# minigame.net
KiCad netlist of a schematic drawn in EAGLE
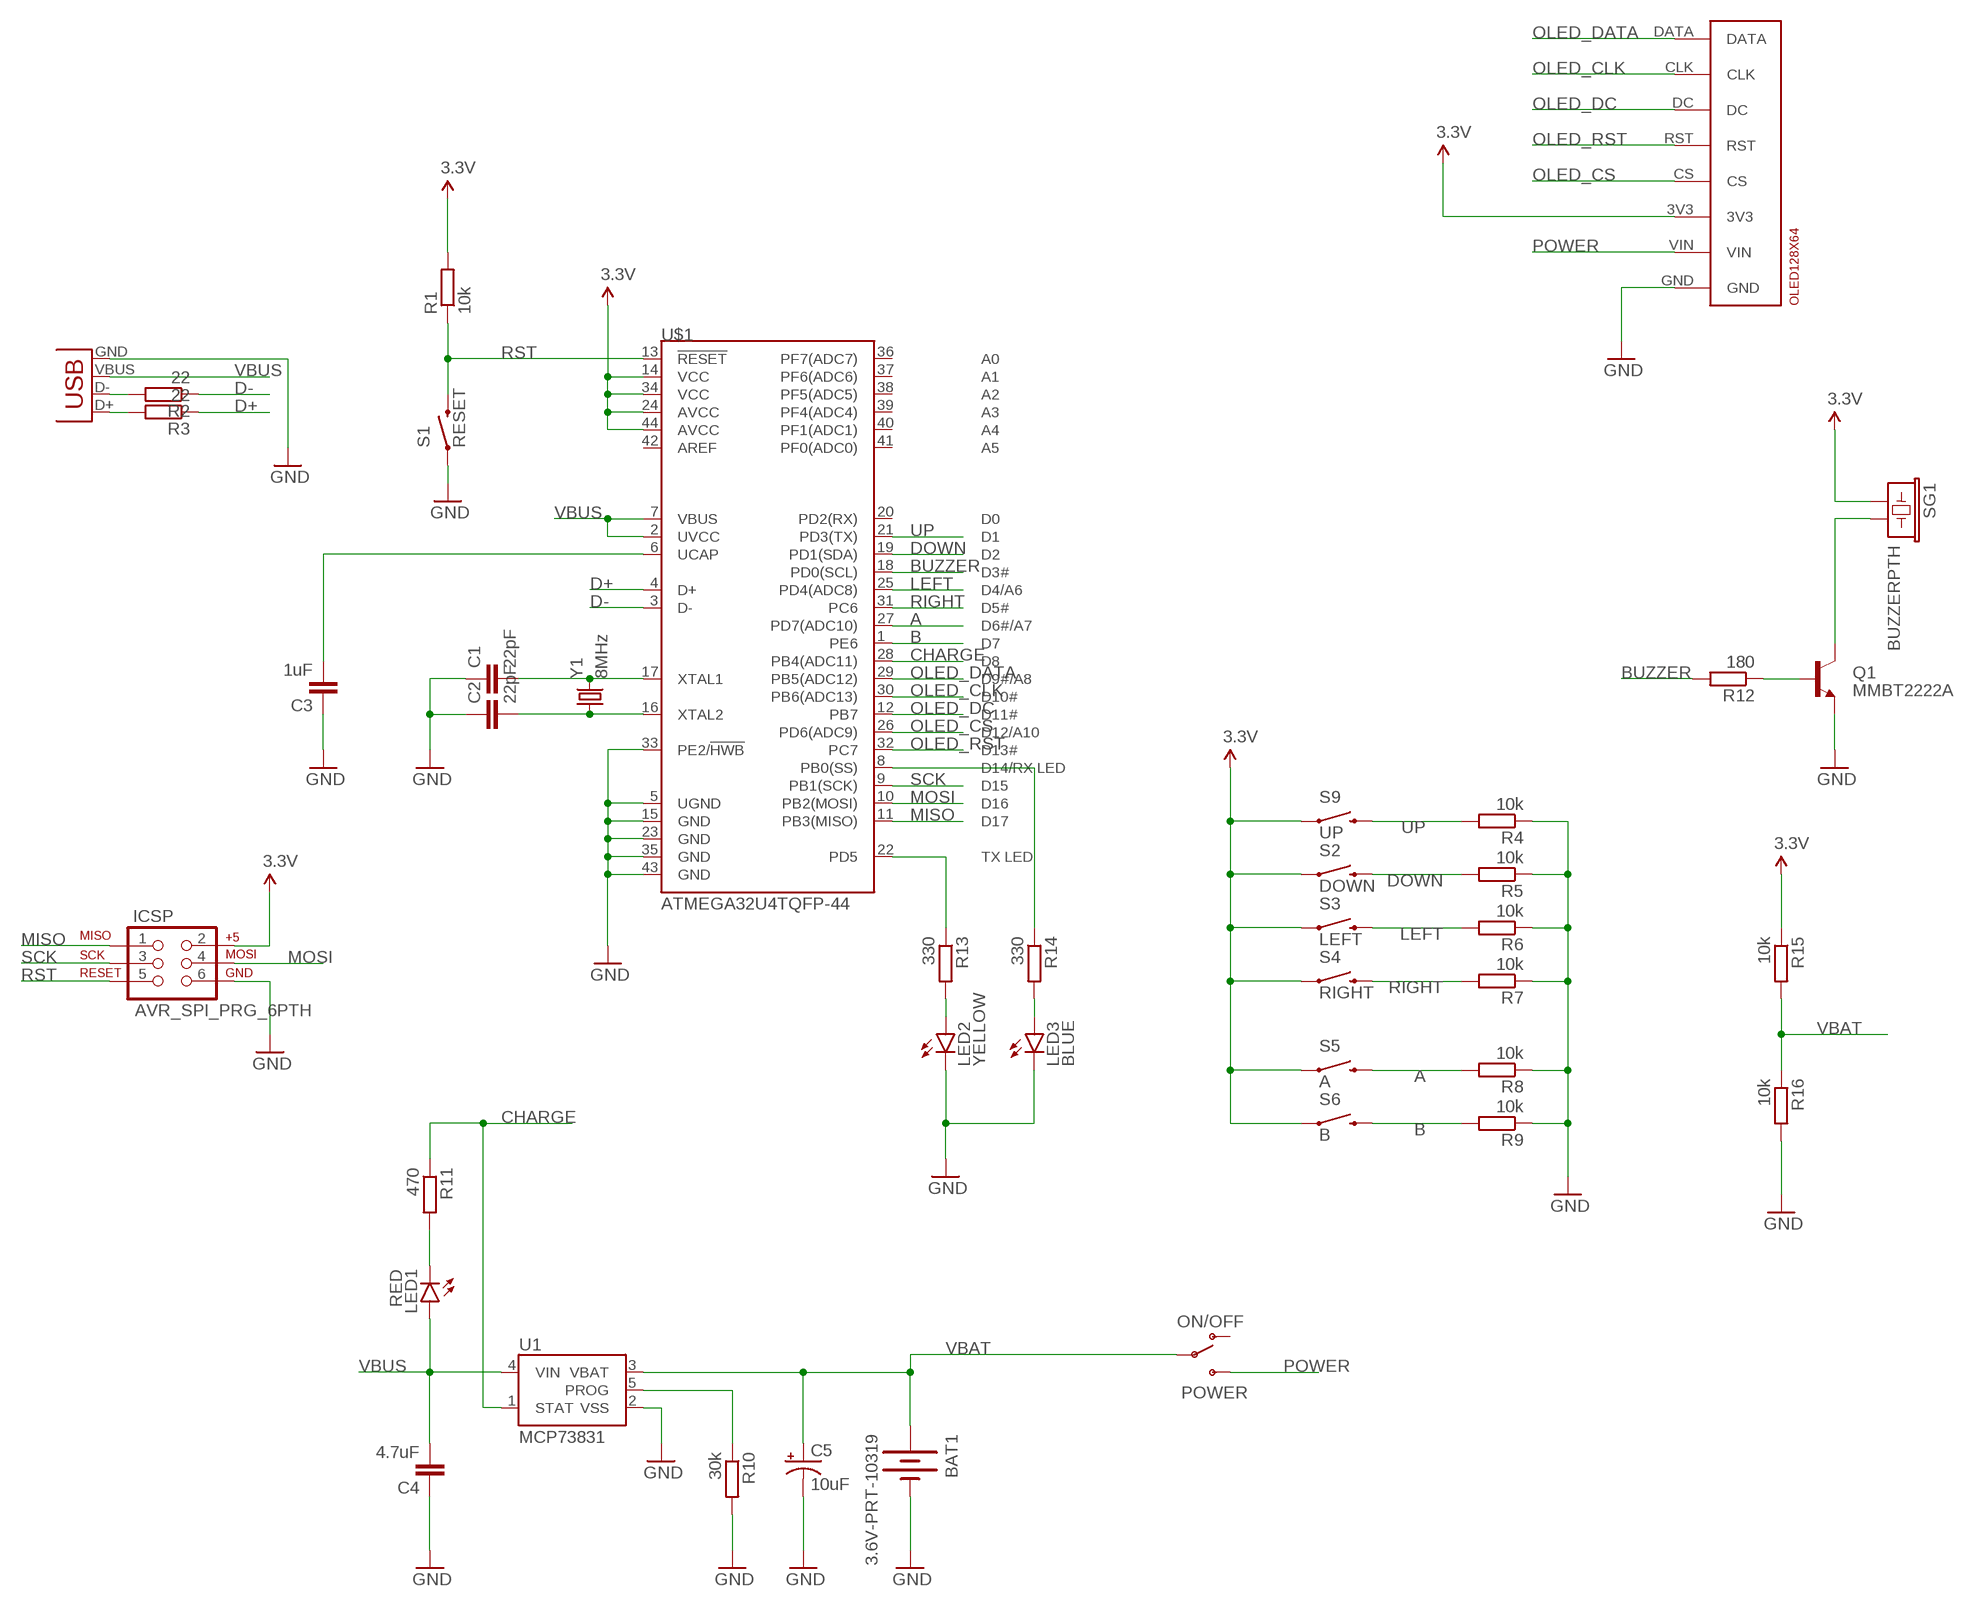
[diagram p0: schematic, sheet 1]

(export (version "E")
  (design (tool "Eeschema 10.0.6"))
  (components
    (comp (ref "BAT1")
      (value "3.6V-PRT-10319")
      (footprint "eagle-import:BATTCON_245MM_PTH")
      (libsource (lib "eagle-import") (part "BATTERY245PTH"))
    )
    (comp (ref "C1")
      (value "22pF")
      (footprint "eagle-import:1206")
      (libsource (lib "eagle-import") (part "CAP1206"))
    )
    (comp (ref "C2")
      (value "22pF")
      (footprint "eagle-import:1206")
      (libsource (lib "eagle-import") (part "CAP1206"))
    )
    (comp (ref "C3")
      (value "1uF")
      (footprint "eagle-import:1206")
      (libsource (lib "eagle-import") (part "CAP1206"))
    )
    (comp (ref "C4")
      (value "4.7uF")
      (footprint "eagle-import:1206")
      (libsource (lib "eagle-import") (part "CAP1206"))
    )
    (comp (ref "C5")
      (value "10uF")
      (footprint "eagle-import:PANASONIC_D")
      (libsource (lib "eagle-import") (part "CAP_POLD"))
    )
    (comp (ref "ICSP")
      (value "AVR_SPI_PRG_6PTH")
      (footprint "eagle-import:2X3")
      (libsource (lib "eagle-import") (part "AVR_SPI_PRG_6PTH"))
    )
    (comp (ref "JP1")
      (value "USB-SMD-NS")
      (footprint "eagle-import:USB-MINIB-NOSTOP")
      (libsource (lib "eagle-import") (part "USB-SMD-NS"))
    )
    (comp (ref "LED1")
      (value "RED")
      (footprint "eagle-import:LED-0603")
      (libsource (lib "eagle-import") (part "LED0603"))
    )
    (comp (ref "LED2")
      (value "YELLOW")
      (footprint "eagle-import:LED-0603")
      (libsource (lib "eagle-import") (part "LED0603"))
    )
    (comp (ref "LED3")
      (value "BLUE")
      (footprint "eagle-import:LED-0603")
      (libsource (lib "eagle-import") (part "LED0603"))
    )
    (comp (ref "OLED128X64")
      (value "OLED128X64-ADAFRUIT938")
      (footprint "eagle-import:938")
      (libsource (lib "eagle-import") (part "OLED128X64-ADAFRUIT938"))
    )
    (comp (ref "POWER")
      (value "ON/OFF")
      (footprint "eagle-import:AYZ0202")
      (libsource (lib "eagle-import") (part "SWITCH-SPDTSMD"))
    )
    (comp (ref "Q1")
      (value "MMBT2222A")
      (footprint "eagle-import:SOT23-3")
      (libsource (lib "eagle-import") (part "TRANSISTOR_NPNMMBT2222A"))
    )
    (comp (ref "R1")
      (value "10k")
      (footprint "eagle-import:M0805")
      (libsource (lib "eagle-import") (part "R-EU_M0805"))
    )
    (comp (ref "R2")
      (value "22")
      (footprint "eagle-import:M0805")
      (libsource (lib "eagle-import") (part "R-EU_M0805"))
    )
    (comp (ref "R3")
      (value "22")
      (footprint "eagle-import:M0805")
      (libsource (lib "eagle-import") (part "R-EU_M0805"))
    )
    (comp (ref "R4")
      (value "10k")
      (footprint "eagle-import:M0805")
      (libsource (lib "eagle-import") (part "R-EU_M0805"))
    )
    (comp (ref "R5")
      (value "10k")
      (footprint "eagle-import:M0805")
      (libsource (lib "eagle-import") (part "R-EU_M0805"))
    )
    (comp (ref "R6")
      (value "10k")
      (footprint "eagle-import:M0805")
      (libsource (lib "eagle-import") (part "R-EU_M0805"))
    )
    (comp (ref "R7")
      (value "10k")
      (footprint "eagle-import:M0805")
      (libsource (lib "eagle-import") (part "R-EU_M0805"))
    )
    (comp (ref "R8")
      (value "10k")
      (footprint "eagle-import:M0805")
      (libsource (lib "eagle-import") (part "R-EU_M0805"))
    )
    (comp (ref "R9")
      (value "10k")
      (footprint "eagle-import:M0805")
      (libsource (lib "eagle-import") (part "R-EU_M0805"))
    )
    (comp (ref "R10")
      (value "30k")
      (footprint "eagle-import:M0805")
      (libsource (lib "eagle-import") (part "R-EU_M0805"))
    )
    (comp (ref "R11")
      (value "470")
      (footprint "eagle-import:M0805")
      (libsource (lib "eagle-import") (part "R-EU_M0805"))
    )
    (comp (ref "R12")
      (value "180")
      (footprint "eagle-import:M0805")
      (libsource (lib "eagle-import") (part "R-EU_M0805"))
    )
    (comp (ref "R13")
      (value "330")
      (footprint "eagle-import:M0805")
      (libsource (lib "eagle-import") (part "R-EU_M0805"))
    )
    (comp (ref "R14")
      (value "330")
      (footprint "eagle-import:M0805")
      (libsource (lib "eagle-import") (part "R-EU_M0805"))
    )
    (comp (ref "R15")
      (value "10k")
      (footprint "eagle-import:M0805")
      (libsource (lib "eagle-import") (part "R-EU_M0805"))
    )
    (comp (ref "R16")
      (value "10k")
      (footprint "eagle-import:M0805")
      (libsource (lib "eagle-import") (part "R-EU_M0805"))
    )
    (comp (ref "S1")
      (value "RESET")
      (footprint "eagle-import:TACTILE-SWITCH-SMD")
      (libsource (lib "eagle-import") (part "SWITCH-MOMENTARY-2SMD"))
    )
    (comp (ref "S2")
      (value "DOWN")
      (footprint "eagle-import:TACTILE_SWITCH_TALL")
      (libsource (lib "eagle-import") (part "SWITCH-MOMENTARY-2SMD-4"))
    )
    (comp (ref "S3")
      (value "LEFT")
      (footprint "eagle-import:TACTILE_SWITCH_TALL")
      (libsource (lib "eagle-import") (part "SWITCH-MOMENTARY-2SMD-4"))
    )
    (comp (ref "S4")
      (value "RIGHT")
      (footprint "eagle-import:TACTILE_SWITCH_TALL")
      (libsource (lib "eagle-import") (part "SWITCH-MOMENTARY-2SMD-4"))
    )
    (comp (ref "S5")
      (value "A")
      (footprint "eagle-import:TACTILE_SWITCH_TALL")
      (libsource (lib "eagle-import") (part "SWITCH-MOMENTARY-2SMD-4"))
    )
    (comp (ref "S6")
      (value "B")
      (footprint "eagle-import:TACTILE_SWITCH_TALL")
      (libsource (lib "eagle-import") (part "SWITCH-MOMENTARY-2SMD-4"))
    )
    (comp (ref "S9")
      (value "UP")
      (footprint "eagle-import:TACTILE_SWITCH_TALL")
      (libsource (lib "eagle-import") (part "SWITCH-MOMENTARY-2SMD-4"))
    )
    (comp (ref "SG1")
      (value "BUZZERPTH")
      (footprint "eagle-import:BUZZER-12MM")
      (libsource (lib "eagle-import") (part "BUZZERPTH"))
    )
    (comp (ref "U$1")
      (value "ATMEGA32U4TQFP-44")
      (footprint "eagle-import:TQFP44")
      (libsource (lib "eagle-import") (part "ATMEGA32U4TQFP-44"))
    )
    (comp (ref "U1")
      (value "MCP73831")
      (footprint "eagle-import:SOT23-5")
      (libsource (lib "eagle-import") (part "MCP73831"))
    )
    (comp (ref "Y1")
      (value "8MHz")
      (footprint "eagle-import:HC49US")
      (libsource (lib "eagle-import") (part "CRYSTALHC49US"))
    )
  )
  (nets
    (net (code "1") (name "/A") (class "Default")
      (node (ref "R8") (pin "2") (pinfunction "2_2") (pintype "passive"))
      (node (ref "S5") (pin "B2") (pinfunction "2_B2") (pintype "passive"))
      (node (ref "U$1") (pin "27") (pinfunction "PD7(ADC10)_27") (pintype "bidirectional"))
    )
    (net (code "2") (name "/B") (class "Default")
      (node (ref "R9") (pin "2") (pinfunction "2_2") (pintype "passive"))
      (node (ref "S6") (pin "B2") (pinfunction "2_B2") (pintype "passive"))
      (node (ref "U$1") (pin "1") (pinfunction "PE6_1") (pintype "bidirectional"))
    )
    (net (code "3") (name "/BUZZER") (class "Default")
      (node (ref "R12") (pin "2") (pinfunction "2_2") (pintype "passive"))
      (node (ref "U$1") (pin "18") (pinfunction "PD0(SCL)_18") (pintype "bidirectional"))
    )
    (net (code "4") (name "/CHARGE") (class "Default")
      (node (ref "R11") (pin "1") (pinfunction "1_1") (pintype "passive"))
      (node (ref "U$1") (pin "28") (pinfunction "PB4(ADC11)_28") (pintype "bidirectional"))
      (node (ref "U1") (pin "1") (pinfunction "STAT_1") (pintype "output"))
    )
    (net (code "5") (name "/D+") (class "Default")
      (node (ref "R3") (pin "1") (pinfunction "1_1") (pintype "passive"))
      (node (ref "U$1") (pin "4") (pinfunction "D+_4") (pintype "bidirectional"))
    )
    (net (code "6") (name "/D-") (class "Default")
      (node (ref "R2") (pin "1") (pinfunction "1_1") (pintype "passive"))
      (node (ref "U$1") (pin "3") (pinfunction "D-_3") (pintype "bidirectional"))
    )
    (net (code "7") (name "/DOWN") (class "Default")
      (node (ref "R5") (pin "2") (pinfunction "2_2") (pintype "passive"))
      (node (ref "S2") (pin "B2") (pinfunction "2_B2") (pintype "passive"))
      (node (ref "U$1") (pin "19") (pinfunction "PD1(SDA)_19") (pintype "bidirectional"))
    )
    (net (code "8") (name "/LEFT") (class "Default")
      (node (ref "R6") (pin "2") (pinfunction "2_2") (pintype "passive"))
      (node (ref "S3") (pin "B2") (pinfunction "2_B2") (pintype "passive"))
      (node (ref "U$1") (pin "25") (pinfunction "PD4(ADC8)_25") (pintype "bidirectional"))
    )
    (net (code "9") (name "/MISO") (class "Default")
      (node (ref "ICSP") (pin "1") (pinfunction "1_1") (pintype "passive"))
      (node (ref "U$1") (pin "11") (pinfunction "PB3(MISO)_11") (pintype "bidirectional"))
    )
    (net (code "10") (name "/MOSI") (class "Default")
      (node (ref "ICSP") (pin "4") (pinfunction "4_4") (pintype "passive"))
      (node (ref "U$1") (pin "10") (pinfunction "PB2(MOSI)_10") (pintype "bidirectional"))
    )
    (net (code "11") (name "/OLED_CLK") (class "Default")
      (node (ref "OLED128X64") (pin "CLK") (pinfunction "CLK_CLK") (pintype "bidirectional"))
      (node (ref "U$1") (pin "30") (pinfunction "PB6(ADC13)_30") (pintype "bidirectional"))
    )
    (net (code "12") (name "/OLED_CS") (class "Default")
      (node (ref "OLED128X64") (pin "CS") (pinfunction "CS_CS") (pintype "bidirectional"))
      (node (ref "U$1") (pin "26") (pinfunction "PD6(ADC9)_26") (pintype "bidirectional"))
    )
    (net (code "13") (name "/OLED_DATA") (class "Default")
      (node (ref "OLED128X64") (pin "DATA") (pinfunction "DATA_DATA") (pintype "bidirectional"))
      (node (ref "U$1") (pin "29") (pinfunction "PB5(ADC12)_29") (pintype "bidirectional"))
    )
    (net (code "14") (name "/OLED_DC") (class "Default")
      (node (ref "OLED128X64") (pin "DC") (pinfunction "DC_DC") (pintype "bidirectional"))
      (node (ref "U$1") (pin "12") (pinfunction "PB7_12") (pintype "bidirectional"))
    )
    (net (code "15") (name "/OLED_RST") (class "Default")
      (node (ref "OLED128X64") (pin "RST") (pinfunction "RST_RST") (pintype "bidirectional"))
      (node (ref "U$1") (pin "32") (pinfunction "PC7_32") (pintype "bidirectional"))
    )
    (net (code "16") (name "/POWER") (class "Default")
      (node (ref "OLED128X64") (pin "VIN") (pinfunction "VIN_VIN") (pintype "bidirectional"))
      (node (ref "POWER") (pin "3") (pinfunction "S_3") (pintype "passive"))
    )
    (net (code "17") (name "/RIGHT") (class "Default")
      (node (ref "R7") (pin "2") (pinfunction "2_2") (pintype "passive"))
      (node (ref "S4") (pin "B2") (pinfunction "2_B2") (pintype "passive"))
      (node (ref "U$1") (pin "31") (pinfunction "PC6_31") (pintype "bidirectional"))
    )
    (net (code "18") (name "/RST") (class "Default")
      (node (ref "ICSP") (pin "5") (pinfunction "5_5") (pintype "passive"))
      (node (ref "R1") (pin "1") (pinfunction "1_1") (pintype "passive"))
      (node (ref "S1") (pin "3") (pinfunction "2_3") (pintype "passive"))
      (node (ref "U$1") (pin "13") (pinfunction "~{RESET}_13") (pintype "bidirectional"))
    )
    (net (code "19") (name "/SCK") (class "Default")
      (node (ref "ICSP") (pin "3") (pinfunction "3_3") (pintype "passive"))
      (node (ref "U$1") (pin "9") (pinfunction "PB1(SCK)_9") (pintype "bidirectional"))
    )
    (net (code "20") (name "/UP") (class "Default")
      (node (ref "R4") (pin "2") (pinfunction "2_2") (pintype "passive"))
      (node (ref "S9") (pin "B2") (pinfunction "2_B2") (pintype "passive"))
      (node (ref "U$1") (pin "21") (pinfunction "PD3(TX)_21") (pintype "bidirectional"))
    )
    (net (code "21") (name "/VBAT") (class "Default")
      (node (ref "BAT1") (pin "3") (pinfunction "+_3") (pintype "power_in"))
      (node (ref "C5") (pin "+") (pinfunction "+_+") (pintype "passive"))
      (node (ref "POWER") (pin "2") (pinfunction "P_2") (pintype "passive"))
      (node (ref "R15") (pin "2") (pinfunction "2_2") (pintype "passive"))
      (node (ref "R16") (pin "1") (pinfunction "1_1") (pintype "passive"))
      (node (ref "U1") (pin "3") (pinfunction "VBAT_3") (pintype "power_in"))
    )
    (net (code "22") (name "/VBUS") (class "Default")
      (node (ref "C4") (pin "2") (pinfunction "2_2") (pintype "passive"))
      (node (ref "JP1") (pin "VBUS") (pinfunction "VBUS_VBUS") (pintype "bidirectional"))
      (node (ref "LED1") (pin "A") (pinfunction "A_A") (pintype "passive"))
      (node (ref "U$1") (pin "2") (pinfunction "UVCC_2") (pintype "bidirectional"))
      (node (ref "U$1") (pin "7") (pinfunction "VBUS_7") (pintype "bidirectional"))
      (node (ref "U1") (pin "4") (pinfunction "VIN_4") (pintype "power_in"))
    )
    (net (code "23") (name "3.3V") (class "Default")
      (node (ref "ICSP") (pin "2") (pinfunction "2_2") (pintype "passive"))
      (node (ref "OLED128X64") (pin "3V3") (pinfunction "3V3_3V3") (pintype "bidirectional"))
      (node (ref "R1") (pin "2") (pinfunction "2_2") (pintype "passive"))
      (node (ref "R15") (pin "1") (pinfunction "1_1") (pintype "passive"))
      (node (ref "S2") (pin "A2") (pinfunction "1_A2") (pintype "passive"))
      (node (ref "S3") (pin "A2") (pinfunction "1_A2") (pintype "passive"))
      (node (ref "S4") (pin "A2") (pinfunction "1_A2") (pintype "passive"))
      (node (ref "S5") (pin "A2") (pinfunction "1_A2") (pintype "passive"))
      (node (ref "S6") (pin "A2") (pinfunction "1_A2") (pintype "passive"))
      (node (ref "S9") (pin "A2") (pinfunction "1_A2") (pintype "passive"))
      (node (ref "SG1") (pin "+") (pinfunction "1_+") (pintype "passive"))
      (node (ref "U$1") (pin "14") (pinfunction "VCC_14") (pintype "bidirectional"))
      (node (ref "U$1") (pin "24") (pinfunction "AVCC_24") (pintype "bidirectional"))
      (node (ref "U$1") (pin "34") (pinfunction "VCC_34") (pintype "bidirectional"))
      (node (ref "U$1") (pin "44") (pinfunction "AVCC_44") (pintype "bidirectional"))
    )
    (net (code "24") (name "GND") (class "Default")
      (node (ref "BAT1") (pin "2") (pinfunction "-_2") (pintype "power_in"))
      (node (ref "C1") (pin "1") (pinfunction "1_1") (pintype "passive"))
      (node (ref "C2") (pin "1") (pinfunction "1_1") (pintype "passive"))
      (node (ref "C3") (pin "1") (pinfunction "1_1") (pintype "passive"))
      (node (ref "C4") (pin "1") (pinfunction "1_1") (pintype "passive"))
      (node (ref "C5") (pin "-") (pinfunction "-_-") (pintype "passive"))
      (node (ref "ICSP") (pin "6") (pinfunction "6_6") (pintype "passive"))
      (node (ref "JP1") (pin "GND") (pinfunction "GND_GND") (pintype "bidirectional"))
      (node (ref "LED2") (pin "C") (pinfunction "C_C") (pintype "passive"))
      (node (ref "LED3") (pin "C") (pinfunction "C_C") (pintype "passive"))
      (node (ref "OLED128X64") (pin "GND") (pinfunction "GND_GND") (pintype "bidirectional"))
      (node (ref "Q1") (pin "2") (pinfunction "E_2") (pintype "passive"))
      (node (ref "R10") (pin "2") (pinfunction "2_2") (pintype "passive"))
      (node (ref "R16") (pin "2") (pinfunction "2_2") (pintype "passive"))
      (node (ref "R4") (pin "1") (pinfunction "1_1") (pintype "passive"))
      (node (ref "R5") (pin "1") (pinfunction "1_1") (pintype "passive"))
      (node (ref "R6") (pin "1") (pinfunction "1_1") (pintype "passive"))
      (node (ref "R7") (pin "1") (pinfunction "1_1") (pintype "passive"))
      (node (ref "R8") (pin "1") (pinfunction "1_1") (pintype "passive"))
      (node (ref "R9") (pin "1") (pinfunction "1_1") (pintype "passive"))
      (node (ref "S1") (pin "1") (pinfunction "1_1") (pintype "passive"))
      (node (ref "U$1") (pin "15") (pinfunction "GND_15") (pintype "bidirectional"))
      (node (ref "U$1") (pin "23") (pinfunction "GND_23") (pintype "bidirectional"))
      (node (ref "U$1") (pin "33") (pinfunction "PE2/~{HWB}_33") (pintype "bidirectional"))
      (node (ref "U$1") (pin "35") (pinfunction "GND_35") (pintype "bidirectional"))
      (node (ref "U$1") (pin "43") (pinfunction "GND_43") (pintype "bidirectional"))
      (node (ref "U$1") (pin "5") (pinfunction "UGND_5") (pintype "bidirectional"))
      (node (ref "U1") (pin "2") (pinfunction "VSS_2") (pintype "power_in"))
    )
    (net (code "25") (name "Net-(JP1-PadD+)") (class "Default")
      (node (ref "JP1") (pin "D+") (pinfunction "D+_D+") (pintype "bidirectional"))
      (node (ref "R3") (pin "2") (pinfunction "2_2") (pintype "passive"))
    )
    (net (code "26") (name "Net-(JP1-PadD-)") (class "Default")
      (node (ref "JP1") (pin "D-") (pinfunction "D-_D-") (pintype "bidirectional"))
      (node (ref "R2") (pin "2") (pinfunction "2_2") (pintype "passive"))
    )
    (net (code "27") (name "Net-(LED1-PadC)") (class "Default")
      (node (ref "LED1") (pin "C") (pinfunction "C_C") (pintype "passive"))
      (node (ref "R11") (pin "2") (pinfunction "2_2") (pintype "passive"))
    )
    (net (code "28") (name "Net-(LED2-PadA)") (class "Default")
      (node (ref "LED2") (pin "A") (pinfunction "A_A") (pintype "passive"))
      (node (ref "R13") (pin "2") (pinfunction "2_2") (pintype "passive"))
    )
    (net (code "29") (name "Net-(LED3-PadA)") (class "Default")
      (node (ref "LED3") (pin "A") (pinfunction "A_A") (pintype "passive"))
      (node (ref "R14") (pin "2") (pinfunction "2_2") (pintype "passive"))
    )
    (net (code "30") (name "Net-(Q1-B)") (class "Default")
      (node (ref "Q1") (pin "1") (pinfunction "B_1") (pintype "passive"))
      (node (ref "R12") (pin "1") (pinfunction "1_1") (pintype "passive"))
    )
    (net (code "31") (name "Net-(Q1-C)") (class "Default")
      (node (ref "Q1") (pin "3") (pinfunction "C_3") (pintype "passive"))
      (node (ref "SG1") (pin "-") (pinfunction "2_-") (pintype "passive"))
    )
    (net (code "32") (name "Net-(U$1-PB0(SS))") (class "Default")
      (node (ref "R14") (pin "1") (pinfunction "1_1") (pintype "passive"))
      (node (ref "U$1") (pin "8") (pinfunction "PB0(SS)_8") (pintype "bidirectional"))
    )
    (net (code "33") (name "Net-(U$1-PD5)") (class "Default")
      (node (ref "R13") (pin "1") (pinfunction "1_1") (pintype "passive"))
      (node (ref "U$1") (pin "22") (pinfunction "PD5_22") (pintype "bidirectional"))
    )
    (net (code "34") (name "Net-(U$1-UCAP)") (class "Default")
      (node (ref "C3") (pin "2") (pinfunction "2_2") (pintype "passive"))
      (node (ref "U$1") (pin "6") (pinfunction "UCAP_6") (pintype "bidirectional"))
    )
    (net (code "35") (name "Net-(U$1-XTAL1)") (class "Default")
      (node (ref "C1") (pin "2") (pinfunction "2_2") (pintype "passive"))
      (node (ref "U$1") (pin "17") (pinfunction "XTAL1_17") (pintype "bidirectional"))
      (node (ref "Y1") (pin "2") (pinfunction "2_2") (pintype "passive"))
    )
    (net (code "36") (name "Net-(U$1-XTAL2)") (class "Default")
      (node (ref "C2") (pin "2") (pinfunction "2_2") (pintype "passive"))
      (node (ref "U$1") (pin "16") (pinfunction "XTAL2_16") (pintype "bidirectional"))
      (node (ref "Y1") (pin "1") (pinfunction "1_1") (pintype "passive"))
    )
    (net (code "37") (name "Net-(U1-PROG)") (class "Default")
      (node (ref "R10") (pin "1") (pinfunction "1_1") (pintype "passive"))
      (node (ref "U1") (pin "5") (pinfunction "PROG_5") (pintype "input"))
    )
    (net (code "38") (name "unconnected-(POWER-O-Pad1)") (class "Default")
      (node (ref "POWER") (pin "1") (pinfunction "O_1") (pintype "passive"))
    )
    (net (code "39") (name "unconnected-(U$1-AREF-Pad42)") (class "Default")
      (node (ref "U$1") (pin "42") (pinfunction "AREF_42") (pintype "bidirectional"))
    )
    (net (code "40") (name "unconnected-(U$1-PD2(RX)-Pad20)") (class "Default")
      (node (ref "U$1") (pin "20") (pinfunction "PD2(RX)_20") (pintype "bidirectional"))
    )
    (net (code "41") (name "unconnected-(U$1-PF0(ADC0)-Pad41)") (class "Default")
      (node (ref "U$1") (pin "41") (pinfunction "PF0(ADC0)_41") (pintype "bidirectional"))
    )
    (net (code "42") (name "unconnected-(U$1-PF1(ADC1)-Pad40)") (class "Default")
      (node (ref "U$1") (pin "40") (pinfunction "PF1(ADC1)_40") (pintype "bidirectional"))
    )
    (net (code "43") (name "unconnected-(U$1-PF4(ADC4)-Pad39)") (class "Default")
      (node (ref "U$1") (pin "39") (pinfunction "PF4(ADC4)_39") (pintype "bidirectional"))
    )
    (net (code "44") (name "unconnected-(U$1-PF5(ADC5)-Pad38)") (class "Default")
      (node (ref "U$1") (pin "38") (pinfunction "PF5(ADC5)_38") (pintype "bidirectional"))
    )
    (net (code "45") (name "unconnected-(U$1-PF6(ADC6)-Pad37)") (class "Default")
      (node (ref "U$1") (pin "37") (pinfunction "PF6(ADC6)_37") (pintype "bidirectional"))
    )
    (net (code "46") (name "unconnected-(U$1-PF7(ADC7)-Pad36)") (class "Default")
      (node (ref "U$1") (pin "36") (pinfunction "PF7(ADC7)_36") (pintype "bidirectional"))
    )
  )
)
